# board.net
KiCad netlist of a schematic drawn in EAGLE
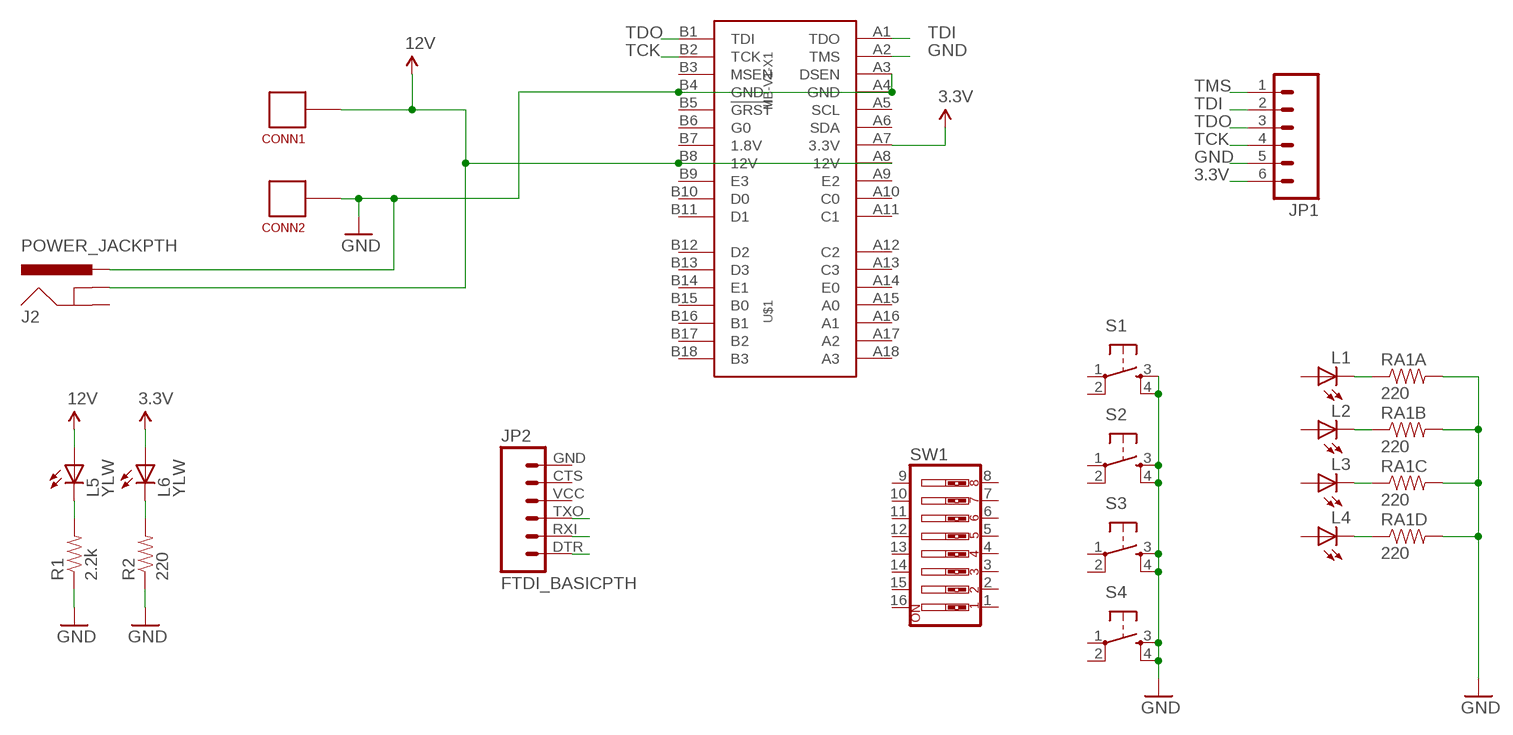
[diagram p0: schematic, sheet 1]

(export (version "E")
  (design (tool "Eeschema 10.0.6"))
  (components
    (comp (ref "CONN1")
      (value "CONNECTOR18AWG")
      (footprint "eagle-import:HOLE_18AWG")
      (libsource (lib "eagle-import") (part "CONNECTOR18AWG"))
    )
    (comp (ref "CONN2")
      (value "CONNECTOR18AWG")
      (footprint "eagle-import:HOLE_18AWG")
      (libsource (lib "eagle-import") (part "CONNECTOR18AWG"))
    )
    (comp (ref "J2")
      (value "POWER_JACKPTH")
      (footprint "eagle-import:POWER_JACK_PTH")
      (libsource (lib "eagle-import") (part "POWER_JACKPTH"))
    )
    (comp (ref "JP1")
      (value "M06LOCK")
      (footprint "eagle-import:1X06_LOCK")
      (libsource (lib "eagle-import") (part "M06LOCK"))
    )
    (comp (ref "JP2")
      (value "FTDI_BASICPTH")
      (footprint "eagle-import:FTDI_BASIC")
      (libsource (lib "eagle-import") (part "FTDI_BASICPTH"))
    )
    (comp (ref "L1")
      (value "LED0603")
      (footprint "eagle-import:0603_LED")
      (libsource (lib "eagle-import") (part "LED0603"))
    )
    (comp (ref "L2")
      (value "LED0603")
      (footprint "eagle-import:0603_LED")
      (libsource (lib "eagle-import") (part "LED0603"))
    )
    (comp (ref "L3")
      (value "LED0603")
      (footprint "eagle-import:0603_LED")
      (libsource (lib "eagle-import") (part "LED0603"))
    )
    (comp (ref "L4")
      (value "LED0603")
      (footprint "eagle-import:0603_LED")
      (libsource (lib "eagle-import") (part "LED0603"))
    )
    (comp (ref "L5")
      (value "YLW")
      (footprint "eagle-import:0603_LED")
      (libsource (lib "eagle-import") (part "LED0603"))
    )
    (comp (ref "L6")
      (value "YLW")
      (footprint "eagle-import:0603_LED")
      (libsource (lib "eagle-import") (part "LED0603"))
    )
    (comp (ref "R1")
      (value "2.2k")
      (footprint "eagle-import:0603-RES")
      (libsource (lib "eagle-import") (part "RESISTOR0603"))
    )
    (comp (ref "R2")
      (value "220")
      (footprint "eagle-import:0603-RES")
      (libsource (lib "eagle-import") (part "RESISTOR0603"))
    )
    (comp (ref "RA1")
      (value "220")
      (footprint "eagle-import:0603-ARV")
      (libsource (lib "eagle-import") (part "RESISTOR_ARRAY0603_X4"))
    )
    (comp (ref "S1")
      (value "TAC_SWITCHPTH")
      (footprint "eagle-import:TACTILE-PTH")
      (libsource (lib "eagle-import") (part "TAC_SWITCHPTH"))
    )
    (comp (ref "S2")
      (value "TAC_SWITCHPTH")
      (footprint "eagle-import:TACTILE-PTH")
      (libsource (lib "eagle-import") (part "TAC_SWITCHPTH"))
    )
    (comp (ref "S3")
      (value "TAC_SWITCHPTH")
      (footprint "eagle-import:TACTILE-PTH")
      (libsource (lib "eagle-import") (part "TAC_SWITCHPTH"))
    )
    (comp (ref "S4")
      (value "TAC_SWITCHPTH")
      (footprint "eagle-import:TACTILE-PTH")
      (libsource (lib "eagle-import") (part "TAC_SWITCHPTH"))
    )
    (comp (ref "SW1")
      (value "SW_DIP-8")
      (footprint "eagle-import:DIPSWITCH-08")
      (libsource (lib "eagle-import") (part "SW_DIP-8"))
    )
    (comp (ref "U$1")
      (value "MB-V1-X1")
      (footprint "eagle-import:PCIE-X1-EDGE")
      (libsource (lib "eagle-import") (part "MB-V1-X1"))
    )
  )
  (nets
    (net (code "1") (name "/TCK") (class "Default")
      (node (ref "JP1") (pin "4") (pinfunction "4_4") (pintype "passive"))
      (node (ref "U$1") (pin "B2") (pinfunction "TCK_B2") (pintype "bidirectional"))
    )
    (net (code "2") (name "/TDI") (class "Default")
      (node (ref "JP1") (pin "2") (pinfunction "2_2") (pintype "passive"))
      (node (ref "U$1") (pin "A1") (pinfunction "TDO_A1") (pintype "bidirectional"))
    )
    (net (code "3") (name "/TDO") (class "Default")
      (node (ref "JP1") (pin "3") (pinfunction "3_3") (pintype "passive"))
      (node (ref "U$1") (pin "B1") (pinfunction "TDI_B1") (pintype "bidirectional"))
    )
    (net (code "4") (name "/TMS") (class "Default")
      (node (ref "JP1") (pin "1") (pinfunction "1_1") (pintype "passive"))
    )
    (net (code "5") (name "3.3V") (class "Default")
      (node (ref "JP1") (pin "6") (pinfunction "6_6") (pintype "passive"))
      (node (ref "L6") (pin "A") (pinfunction "A_A") (pintype "passive"))
      (node (ref "U$1") (pin "A7") (pinfunction "3.3V_A7") (pintype "bidirectional"))
    )
    (net (code "6") (name "12V") (class "Default")
      (node (ref "CONN1") (pin "P$1") (pinfunction "P_P$1") (pintype "bidirectional"))
      (node (ref "J2") (pin "GNDBREAK") (pinfunction "GNDBREAK_GNDBREAK") (pintype "bidirectional"))
      (node (ref "L5") (pin "A") (pinfunction "A_A") (pintype "passive"))
      (node (ref "U$1") (pin "A8") (pinfunction "12V_A8") (pintype "bidirectional"))
      (node (ref "U$1") (pin "B8") (pinfunction "12V_B8") (pintype "bidirectional"))
    )
    (net (code "7") (name "GND") (class "Default")
      (node (ref "CONN2") (pin "P$1") (pinfunction "P_P$1") (pintype "bidirectional"))
      (node (ref "J2") (pin "PWR") (pinfunction "PWR_PWR") (pintype "bidirectional"))
      (node (ref "JP1") (pin "5") (pinfunction "5_5") (pintype "passive"))
      (node (ref "R1") (pin "1") (pinfunction "1_1") (pintype "passive"))
      (node (ref "R2") (pin "1") (pinfunction "1_1") (pintype "passive"))
      (node (ref "RA1") (pin "5") (pinfunction "2_5") (pintype "passive"))
      (node (ref "RA1") (pin "6") (pinfunction "2_6") (pintype "passive"))
      (node (ref "RA1") (pin "7") (pinfunction "2_7") (pintype "passive"))
      (node (ref "RA1") (pin "8") (pinfunction "2_8") (pintype "passive"))
      (node (ref "S1") (pin "3") (pinfunction "3_3") (pintype "passive"))
      (node (ref "S1") (pin "4") (pinfunction "4_4") (pintype "passive"))
      (node (ref "S2") (pin "3") (pinfunction "3_3") (pintype "passive"))
      (node (ref "S2") (pin "4") (pinfunction "4_4") (pintype "passive"))
      (node (ref "S3") (pin "3") (pinfunction "3_3") (pintype "passive"))
      (node (ref "S3") (pin "4") (pinfunction "4_4") (pintype "passive"))
      (node (ref "S4") (pin "3") (pinfunction "3_3") (pintype "passive"))
      (node (ref "S4") (pin "4") (pinfunction "4_4") (pintype "passive"))
      (node (ref "U$1") (pin "A2") (pinfunction "TMS_A2") (pintype "bidirectional"))
      (node (ref "U$1") (pin "A3") (pinfunction "DSEN_A3") (pintype "bidirectional"))
      (node (ref "U$1") (pin "A4") (pinfunction "GND_A4") (pintype "bidirectional"))
      (node (ref "U$1") (pin "B4") (pinfunction "GND_B4") (pintype "bidirectional"))
    )
    (net (code "8") (name "Net-(L1-PadC)") (class "Default")
      (node (ref "L1") (pin "C") (pinfunction "C_C") (pintype "passive"))
      (node (ref "RA1") (pin "1") (pinfunction "1_1") (pintype "passive"))
    )
    (net (code "9") (name "Net-(L5-PadC)") (class "Default")
      (node (ref "L5") (pin "C") (pinfunction "C_C") (pintype "passive"))
      (node (ref "R1") (pin "2") (pinfunction "2_2") (pintype "passive"))
    )
    (net (code "10") (name "Net-(L6-PadC)") (class "Default")
      (node (ref "L6") (pin "C") (pinfunction "C_C") (pintype "passive"))
      (node (ref "R2") (pin "2") (pinfunction "2_2") (pintype "passive"))
    )
    (net (code "11") (name "Net-(RA1B-1)") (class "Default")
      (node (ref "L2") (pin "C") (pinfunction "C_C") (pintype "passive"))
      (node (ref "RA1") (pin "2") (pinfunction "1_2") (pintype "passive"))
    )
    (net (code "12") (name "Net-(RA1C-1)") (class "Default")
      (node (ref "L3") (pin "C") (pinfunction "C_C") (pintype "passive"))
      (node (ref "RA1") (pin "3") (pinfunction "1_3") (pintype "passive"))
    )
    (net (code "13") (name "Net-(RA1D-1)") (class "Default")
      (node (ref "L4") (pin "C") (pinfunction "C_C") (pintype "passive"))
      (node (ref "RA1") (pin "4") (pinfunction "1_4") (pintype "passive"))
    )
    (net (code "14") (name "unconnected-(J2-PadGND)") (class "Default")
      (node (ref "J2") (pin "GND") (pinfunction "GND_GND") (pintype "bidirectional"))
    )
    (net (code "15") (name "unconnected-(JP2-1-PadDTR)") (class "Default")
      (node (ref "JP2") (pin "DTR") (pinfunction "1_DTR") (pintype "passive"))
    )
    (net (code "16") (name "unconnected-(JP2-2-PadRXI)") (class "Default")
      (node (ref "JP2") (pin "RXI") (pinfunction "2_RXI") (pintype "passive"))
    )
    (net (code "17") (name "unconnected-(JP2-3-PadTXO)") (class "Default")
      (node (ref "JP2") (pin "TXO") (pinfunction "3_TXO") (pintype "passive"))
    )
    (net (code "18") (name "unconnected-(JP2-4-PadVCC)") (class "Default")
      (node (ref "JP2") (pin "VCC") (pinfunction "4_VCC") (pintype "passive"))
    )
    (net (code "19") (name "unconnected-(JP2-5-PadCTS)") (class "Default")
      (node (ref "JP2") (pin "CTS") (pinfunction "5_CTS") (pintype "passive"))
    )
    (net (code "20") (name "unconnected-(JP2-6-PadGND)") (class "Default")
      (node (ref "JP2") (pin "GND") (pinfunction "6_GND") (pintype "passive"))
    )
    (net (code "21") (name "unconnected-(L1-PadA)") (class "Default")
      (node (ref "L1") (pin "A") (pinfunction "A_A") (pintype "passive"))
    )
    (net (code "22") (name "unconnected-(L2-PadA)") (class "Default")
      (node (ref "L2") (pin "A") (pinfunction "A_A") (pintype "passive"))
    )
    (net (code "23") (name "unconnected-(L3-PadA)") (class "Default")
      (node (ref "L3") (pin "A") (pinfunction "A_A") (pintype "passive"))
    )
    (net (code "24") (name "unconnected-(L4-PadA)") (class "Default")
      (node (ref "L4") (pin "A") (pinfunction "A_A") (pintype "passive"))
    )
    (net (code "25") (name "unconnected-(S1-Pad1)") (class "Default")
      (node (ref "S1") (pin "1") (pinfunction "1_1") (pintype "passive"))
    )
    (net (code "26") (name "unconnected-(S1-Pad2)") (class "Default")
      (node (ref "S1") (pin "2") (pinfunction "2_2") (pintype "passive"))
    )
    (net (code "27") (name "unconnected-(S2-Pad1)") (class "Default")
      (node (ref "S2") (pin "1") (pinfunction "1_1") (pintype "passive"))
    )
    (net (code "28") (name "unconnected-(S2-Pad2)") (class "Default")
      (node (ref "S2") (pin "2") (pinfunction "2_2") (pintype "passive"))
    )
    (net (code "29") (name "unconnected-(S3-Pad1)") (class "Default")
      (node (ref "S3") (pin "1") (pinfunction "1_1") (pintype "passive"))
    )
    (net (code "30") (name "unconnected-(S3-Pad2)") (class "Default")
      (node (ref "S3") (pin "2") (pinfunction "2_2") (pintype "passive"))
    )
    (net (code "31") (name "unconnected-(S4-Pad1)") (class "Default")
      (node (ref "S4") (pin "1") (pinfunction "1_1") (pintype "passive"))
    )
    (net (code "32") (name "unconnected-(S4-Pad2)") (class "Default")
      (node (ref "S4") (pin "2") (pinfunction "2_2") (pintype "passive"))
    )
    (net (code "33") (name "unconnected-(SW1-Pad1)") (class "Default")
      (node (ref "SW1") (pin "1") (pinfunction "1_1") (pintype "passive"))
    )
    (net (code "34") (name "unconnected-(SW1-Pad2)") (class "Default")
      (node (ref "SW1") (pin "2") (pinfunction "2_2") (pintype "passive"))
    )
    (net (code "35") (name "unconnected-(SW1-Pad3)") (class "Default")
      (node (ref "SW1") (pin "3") (pinfunction "3_3") (pintype "passive"))
    )
    (net (code "36") (name "unconnected-(SW1-Pad4)") (class "Default")
      (node (ref "SW1") (pin "4") (pinfunction "4_4") (pintype "passive"))
    )
    (net (code "37") (name "unconnected-(SW1-Pad5)") (class "Default")
      (node (ref "SW1") (pin "5") (pinfunction "5_5") (pintype "passive"))
    )
    (net (code "38") (name "unconnected-(SW1-Pad6)") (class "Default")
      (node (ref "SW1") (pin "6") (pinfunction "6_6") (pintype "passive"))
    )
    (net (code "39") (name "unconnected-(SW1-Pad7)") (class "Default")
      (node (ref "SW1") (pin "7") (pinfunction "7_7") (pintype "passive"))
    )
    (net (code "40") (name "unconnected-(SW1-Pad8)") (class "Default")
      (node (ref "SW1") (pin "8") (pinfunction "8_8") (pintype "passive"))
    )
    (net (code "41") (name "unconnected-(SW1-Pad9)") (class "Default")
      (node (ref "SW1") (pin "9") (pinfunction "9_9") (pintype "passive"))
    )
    (net (code "42") (name "unconnected-(SW1-Pad10)") (class "Default")
      (node (ref "SW1") (pin "10") (pinfunction "10_10") (pintype "passive"))
    )
    (net (code "43") (name "unconnected-(SW1-Pad11)") (class "Default")
      (node (ref "SW1") (pin "11") (pinfunction "11_11") (pintype "passive"))
    )
    (net (code "44") (name "unconnected-(SW1-Pad12)") (class "Default")
      (node (ref "SW1") (pin "12") (pinfunction "12_12") (pintype "passive"))
    )
    (net (code "45") (name "unconnected-(SW1-Pad13)") (class "Default")
      (node (ref "SW1") (pin "13") (pinfunction "13_13") (pintype "passive"))
    )
    (net (code "46") (name "unconnected-(SW1-Pad14)") (class "Default")
      (node (ref "SW1") (pin "14") (pinfunction "14_14") (pintype "passive"))
    )
    (net (code "47") (name "unconnected-(SW1-Pad15)") (class "Default")
      (node (ref "SW1") (pin "15") (pinfunction "15_15") (pintype "passive"))
    )
    (net (code "48") (name "unconnected-(SW1-Pad16)") (class "Default")
      (node (ref "SW1") (pin "16") (pinfunction "16_16") (pintype "passive"))
    )
    (net (code "49") (name "unconnected-(U$1-1.8V-PadB7)") (class "Default")
      (node (ref "U$1") (pin "B7") (pinfunction "1.8V_B7") (pintype "bidirectional"))
    )
    (net (code "50") (name "unconnected-(U$1-A0-PadA15)") (class "Default")
      (node (ref "U$1") (pin "A15") (pinfunction "A0_A15") (pintype "bidirectional"))
    )
    (net (code "51") (name "unconnected-(U$1-A1-PadA16)") (class "Default")
      (node (ref "U$1") (pin "A16") (pinfunction "A1_A16") (pintype "bidirectional"))
    )
    (net (code "52") (name "unconnected-(U$1-A2-PadA17)") (class "Default")
      (node (ref "U$1") (pin "A17") (pinfunction "A2_A17") (pintype "bidirectional"))
    )
    (net (code "53") (name "unconnected-(U$1-A3-PadA18)") (class "Default")
      (node (ref "U$1") (pin "A18") (pinfunction "A3_A18") (pintype "bidirectional"))
    )
    (net (code "54") (name "unconnected-(U$1-B0-PadB15)") (class "Default")
      (node (ref "U$1") (pin "B15") (pinfunction "B0_B15") (pintype "bidirectional"))
    )
    (net (code "55") (name "unconnected-(U$1-B1-PadB16)") (class "Default")
      (node (ref "U$1") (pin "B16") (pinfunction "B1_B16") (pintype "bidirectional"))
    )
    (net (code "56") (name "unconnected-(U$1-B2-PadB17)") (class "Default")
      (node (ref "U$1") (pin "B17") (pinfunction "B2_B17") (pintype "bidirectional"))
    )
    (net (code "57") (name "unconnected-(U$1-B3-PadB18)") (class "Default")
      (node (ref "U$1") (pin "B18") (pinfunction "B3_B18") (pintype "bidirectional"))
    )
    (net (code "58") (name "unconnected-(U$1-C0-PadA10)") (class "Default")
      (node (ref "U$1") (pin "A10") (pinfunction "C0_A10") (pintype "bidirectional"))
    )
    (net (code "59") (name "unconnected-(U$1-C1-PadA11)") (class "Default")
      (node (ref "U$1") (pin "A11") (pinfunction "C1_A11") (pintype "bidirectional"))
    )
    (net (code "60") (name "unconnected-(U$1-C2-PadA12)") (class "Default")
      (node (ref "U$1") (pin "A12") (pinfunction "C2_A12") (pintype "bidirectional"))
    )
    (net (code "61") (name "unconnected-(U$1-C3-PadA13)") (class "Default")
      (node (ref "U$1") (pin "A13") (pinfunction "C3_A13") (pintype "bidirectional"))
    )
    (net (code "62") (name "unconnected-(U$1-D0-PadB10)") (class "Default")
      (node (ref "U$1") (pin "B10") (pinfunction "D0_B10") (pintype "bidirectional"))
    )
    (net (code "63") (name "unconnected-(U$1-D1-PadB11)") (class "Default")
      (node (ref "U$1") (pin "B11") (pinfunction "D1_B11") (pintype "bidirectional"))
    )
    (net (code "64") (name "unconnected-(U$1-D2-PadB12)") (class "Default")
      (node (ref "U$1") (pin "B12") (pinfunction "D2_B12") (pintype "bidirectional"))
    )
    (net (code "65") (name "unconnected-(U$1-D3-PadB13)") (class "Default")
      (node (ref "U$1") (pin "B13") (pinfunction "D3_B13") (pintype "bidirectional"))
    )
    (net (code "66") (name "unconnected-(U$1-E0-PadA14)") (class "Default")
      (node (ref "U$1") (pin "A14") (pinfunction "E0_A14") (pintype "bidirectional"))
    )
    (net (code "67") (name "unconnected-(U$1-E1-PadB14)") (class "Default")
      (node (ref "U$1") (pin "B14") (pinfunction "E1_B14") (pintype "bidirectional"))
    )
    (net (code "68") (name "unconnected-(U$1-E2-PadA9)") (class "Default")
      (node (ref "U$1") (pin "A9") (pinfunction "E2_A9") (pintype "bidirectional"))
    )
    (net (code "69") (name "unconnected-(U$1-E3-PadB9)") (class "Default")
      (node (ref "U$1") (pin "B9") (pinfunction "E3_B9") (pintype "bidirectional"))
    )
    (net (code "70") (name "unconnected-(U$1-G0-PadB6)") (class "Default")
      (node (ref "U$1") (pin "B6") (pinfunction "G0_B6") (pintype "bidirectional"))
    )
    (net (code "71") (name "unconnected-(U$1-MSEN-PadB3)") (class "Default")
      (node (ref "U$1") (pin "B3") (pinfunction "MSEN_B3") (pintype "bidirectional"))
    )
    (net (code "72") (name "unconnected-(U$1-SCL-PadA5)") (class "Default")
      (node (ref "U$1") (pin "A5") (pinfunction "SCL_A5") (pintype "bidirectional"))
    )
    (net (code "73") (name "unconnected-(U$1-SDA-PadA6)") (class "Default")
      (node (ref "U$1") (pin "A6") (pinfunction "SDA_A6") (pintype "bidirectional"))
    )
    (net (code "74") (name "unconnected-(U$1-~{GRST}-PadB5)") (class "Default")
      (node (ref "U$1") (pin "B5") (pinfunction "~{GRST}_B5") (pintype "bidirectional"))
    )
  )
)
